# myDRAMTester.net
KiCad netlist of a schematic drawn in EAGLE
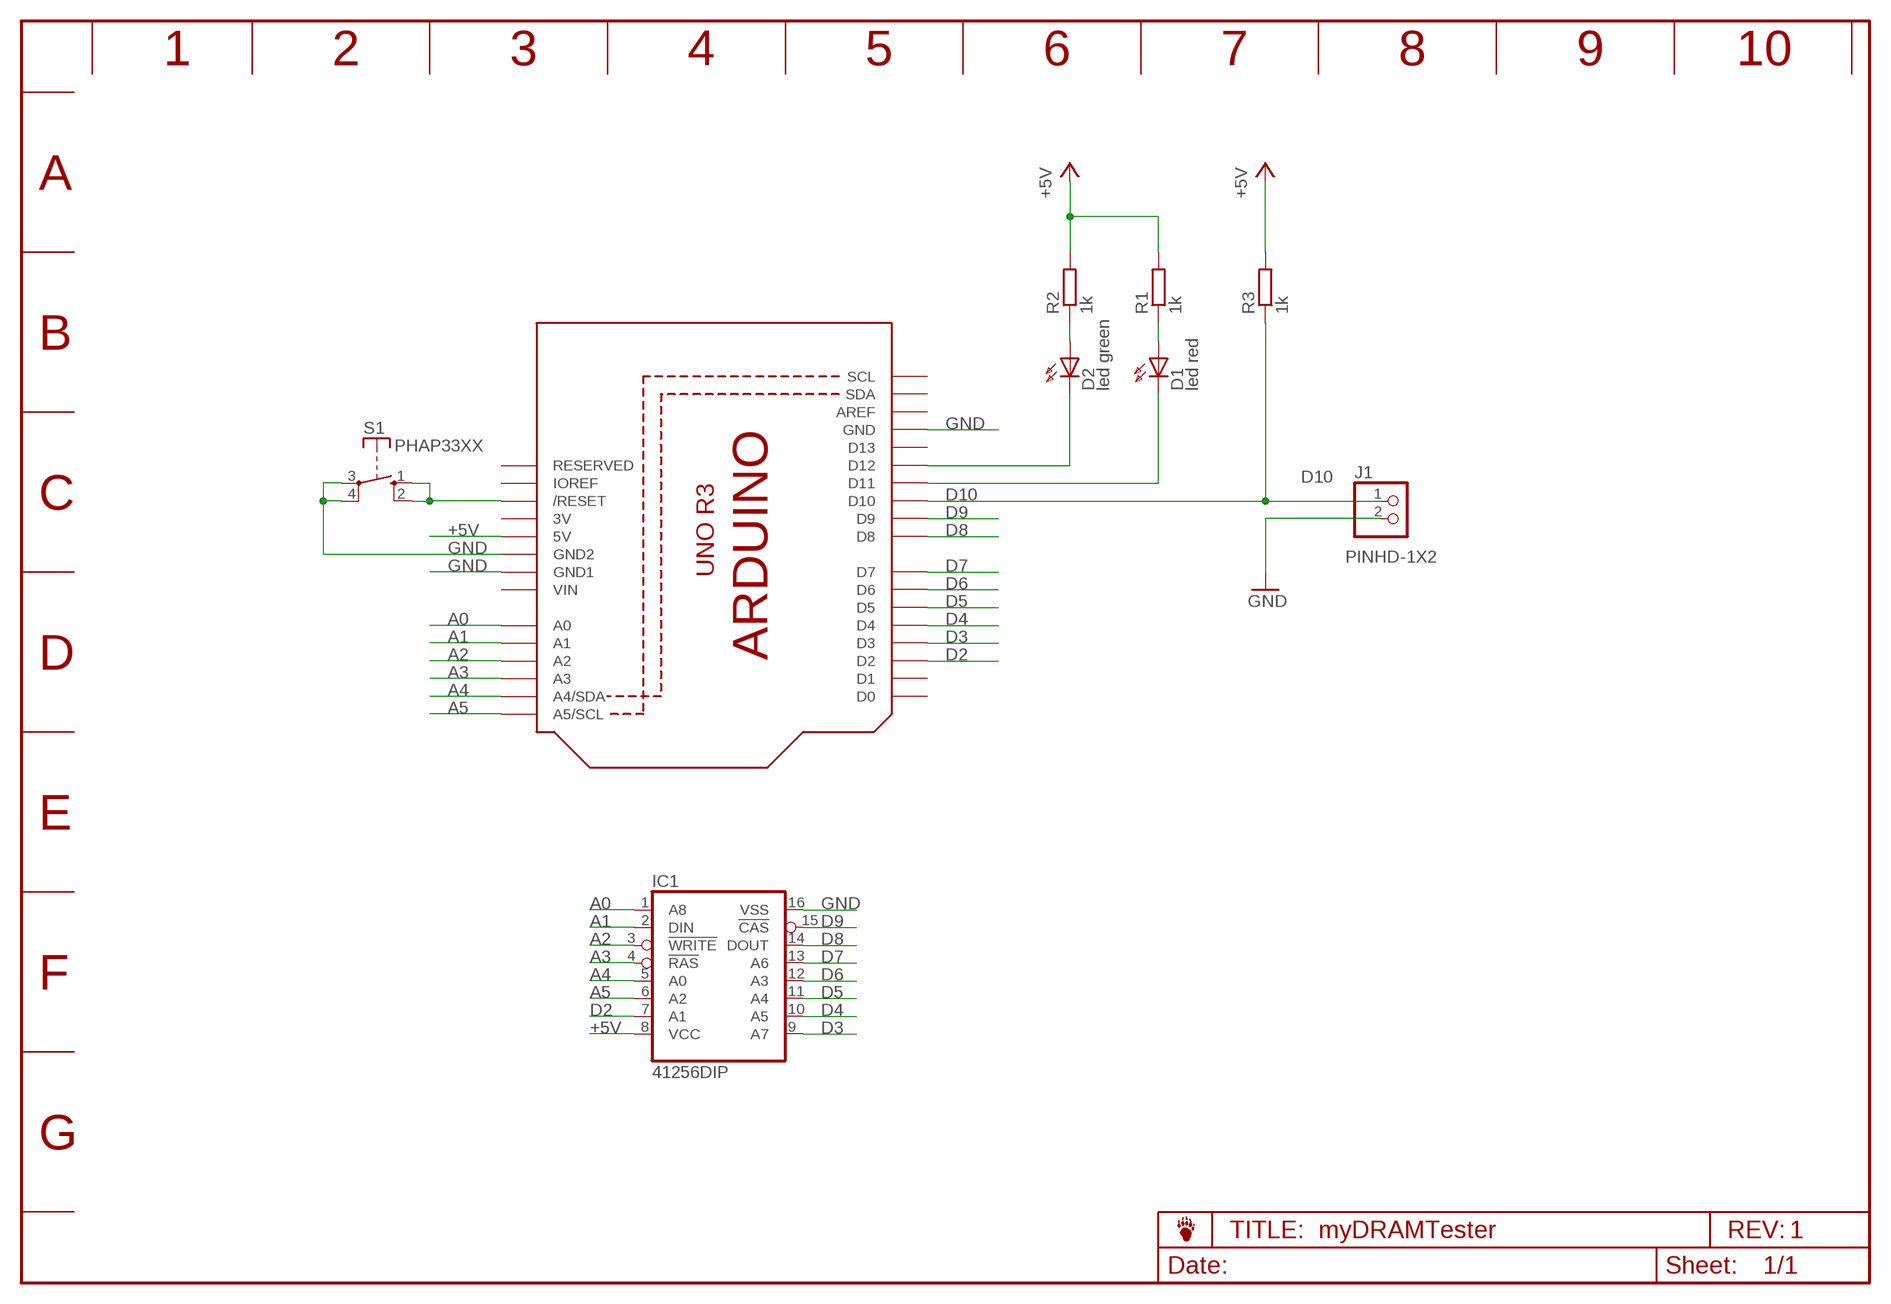
[diagram p0: schematic, sheet 1]

(export (version "E")
  (design (tool "Eeschema 10.0.6"))
  (components
    (comp (ref "D1")
      (value "led red")
      (footprint "eagle-import:LED3MM")
      (libsource (lib "eagle-import") (part "LED3MMS"))
    )
    (comp (ref "D2")
      (value "led green")
      (footprint "eagle-import:LED3MM")
      (libsource (lib "eagle-import") (part "LED3MMS"))
    )
    (comp (ref "IC1")
      (value "41256DIP")
      (footprint "eagle-import:DIL16")
      (libsource (lib "eagle-import") (part "41256DIP"))
    )
    (comp (ref "J1")
      (value "PINHD-1X2")
      (footprint "eagle-import:1X02")
      (libsource (lib "eagle-import") (part "PINHD-1X2"))
    )
    (comp (ref "R1")
      (value "1k")
      (footprint "eagle-import:0207_10")
      (libsource (lib "eagle-import") (part "R-EU_0207/10"))
    )
    (comp (ref "R2")
      (value "1k")
      (footprint "eagle-import:0207_10")
      (libsource (lib "eagle-import") (part "R-EU_0207/10"))
    )
    (comp (ref "R3")
      (value "1k")
      (footprint "eagle-import:0207_10")
      (libsource (lib "eagle-import") (part "R-EU_0207/10"))
    )
    (comp (ref "S1")
      (value "PHAP33XX")
      (footprint "eagle-import:PHAP33XX")
      (libsource (lib "eagle-import") (part "PHAP33XX"))
    )
    (comp (ref "U2")
      (value "ARDUINOR3_BBSMALL")
      (footprint "eagle-import:ARDUINOR3S")
      (libsource (lib "eagle-import") (part "ARDUINOR3_BBSMALL"))
    )
  )
  (nets
    (net (code "1") (name "+5V") (class "Default")
      (node (ref "IC1") (pin "8") (pinfunction "VCC_8") (pintype "input"))
      (node (ref "R1") (pin "2") (pinfunction "2_2") (pintype "passive"))
      (node (ref "R2") (pin "2") (pinfunction "2_2") (pintype "passive"))
      (node (ref "R3") (pin "2") (pinfunction "2_2") (pintype "passive"))
      (node (ref "U2") (pin "5V") (pinfunction "5V_5V") (pintype "power_in"))
    )
    (net (code "2") (name "/3V") (class "Default")
      (node (ref "U2") (pin "3V") (pinfunction "3V_3V") (pintype "power_in"))
    )
    (net (code "3") (name "/A0") (class "Default")
      (node (ref "IC1") (pin "1") (pinfunction "A8_1") (pintype "input"))
      (node (ref "U2") (pin "A0") (pinfunction "A0_A0") (pintype "bidirectional"))
    )
    (net (code "4") (name "/A1") (class "Default")
      (node (ref "IC1") (pin "2") (pinfunction "DIN_2") (pintype "input"))
      (node (ref "U2") (pin "A1") (pinfunction "A1_A1") (pintype "bidirectional"))
    )
    (net (code "5") (name "/A2") (class "Default")
      (node (ref "IC1") (pin "3") (pinfunction "~{WRITE}_3") (pintype "input"))
      (node (ref "U2") (pin "A2") (pinfunction "A2_A2") (pintype "bidirectional"))
    )
    (net (code "6") (name "/A3") (class "Default")
      (node (ref "IC1") (pin "4") (pinfunction "~{RAS}_4") (pintype "input"))
      (node (ref "U2") (pin "A3") (pinfunction "A3_A3") (pintype "bidirectional"))
    )
    (net (code "7") (name "/A4") (class "Default")
      (node (ref "IC1") (pin "5") (pinfunction "A0_5") (pintype "input"))
      (node (ref "U2") (pin "A4") (pinfunction "A4/SDA_A4") (pintype "bidirectional"))
    )
    (net (code "8") (name "/A5") (class "Default")
      (node (ref "IC1") (pin "6") (pinfunction "A2_6") (pintype "input"))
      (node (ref "U2") (pin "A5") (pinfunction "A5/SCL_A5") (pintype "bidirectional"))
    )
    (net (code "9") (name "/D2") (class "Default")
      (node (ref "IC1") (pin "7") (pinfunction "A1_7") (pintype "input"))
      (node (ref "U2") (pin "D2") (pinfunction "D2_D2") (pintype "bidirectional"))
    )
    (net (code "10") (name "/D3") (class "Default")
      (node (ref "IC1") (pin "9") (pinfunction "A7_9") (pintype "tri_state"))
      (node (ref "U2") (pin "D3") (pinfunction "D3_D3") (pintype "bidirectional"))
    )
    (net (code "11") (name "/D4") (class "Default")
      (node (ref "IC1") (pin "10") (pinfunction "A5_10") (pintype "tri_state"))
      (node (ref "U2") (pin "D4") (pinfunction "D4_D4") (pintype "bidirectional"))
    )
    (net (code "12") (name "/D5") (class "Default")
      (node (ref "IC1") (pin "11") (pinfunction "A4_11") (pintype "tri_state"))
      (node (ref "U2") (pin "D5") (pinfunction "D5_D5") (pintype "bidirectional"))
    )
    (net (code "13") (name "/D6") (class "Default")
      (node (ref "IC1") (pin "12") (pinfunction "A3_12") (pintype "tri_state"))
      (node (ref "U2") (pin "D6") (pinfunction "D6_D6") (pintype "bidirectional"))
    )
    (net (code "14") (name "/D7") (class "Default")
      (node (ref "IC1") (pin "13") (pinfunction "A6_13") (pintype "tri_state"))
      (node (ref "U2") (pin "D7") (pinfunction "D7_D7") (pintype "bidirectional"))
    )
    (net (code "15") (name "/D8") (class "Default")
      (node (ref "IC1") (pin "14") (pinfunction "DOUT_14") (pintype "tri_state"))
      (node (ref "U2") (pin "D8") (pinfunction "D8_D8") (pintype "bidirectional"))
    )
    (net (code "16") (name "/D9") (class "Default")
      (node (ref "IC1") (pin "15") (pinfunction "~{CAS}_15") (pintype "tri_state"))
      (node (ref "U2") (pin "D9") (pinfunction "D9_D9") (pintype "bidirectional"))
    )
    (net (code "17") (name "/D10") (class "Default")
      (node (ref "J1") (pin "1") (pinfunction "1_1") (pintype "passive"))
      (node (ref "R3") (pin "1") (pinfunction "1_1") (pintype "passive"))
      (node (ref "U2") (pin "D10") (pinfunction "D10_D10") (pintype "bidirectional"))
    )
    (net (code "18") (name "/VIN") (class "Default")
      (node (ref "U2") (pin "VIN") (pinfunction "VIN_VIN") (pintype "power_in"))
    )
    (net (code "19") (name "GND") (class "Default")
      (node (ref "IC1") (pin "16") (pinfunction "VSS_16") (pintype "tri_state"))
      (node (ref "J1") (pin "2") (pinfunction "2_2") (pintype "passive"))
      (node (ref "S1") (pin "3") (pinfunction "P_3") (pintype "passive"))
      (node (ref "S1") (pin "4") (pinfunction "P_4") (pintype "passive"))
      (node (ref "U2") (pin "GND") (pinfunction "GND_GND") (pintype "power_in"))
      (node (ref "U2") (pin "GND1") (pinfunction "GND1_GND1") (pintype "power_in"))
      (node (ref "U2") (pin "GND2") (pinfunction "GND2_GND2") (pintype "power_in"))
    )
    (net (code "20") (name "Net-(D1-C)") (class "Default")
      (node (ref "D1") (pin "K") (pinfunction "C_K") (pintype "passive"))
      (node (ref "U2") (pin "D11") (pinfunction "D11_D11") (pintype "bidirectional"))
    )
    (net (code "21") (name "Net-(D1-PadA)") (class "Default")
      (node (ref "D1") (pin "A") (pinfunction "A_A") (pintype "passive"))
      (node (ref "R1") (pin "1") (pinfunction "1_1") (pintype "passive"))
    )
    (net (code "22") (name "Net-(D2-C)") (class "Default")
      (node (ref "D2") (pin "K") (pinfunction "C_K") (pintype "passive"))
      (node (ref "U2") (pin "D12") (pinfunction "D12_D12") (pintype "bidirectional"))
    )
    (net (code "23") (name "Net-(D2-PadA)") (class "Default")
      (node (ref "D2") (pin "A") (pinfunction "A_A") (pintype "passive"))
      (node (ref "R2") (pin "1") (pinfunction "1_1") (pintype "passive"))
    )
    (net (code "24") (name "Net-(U2-{slash}RESET)") (class "Default")
      (node (ref "S1") (pin "1") (pinfunction "S_1") (pintype "passive"))
      (node (ref "S1") (pin "2") (pinfunction "S_2") (pintype "passive"))
      (node (ref "U2") (pin "RESET") (pinfunction "/RESET_RESET") (pintype "bidirectional"))
    )
    (net (code "25") (name "unconnected-(U2-PadAREF)") (class "Default")
      (node (ref "U2") (pin "AREF") (pinfunction "AREF_AREF") (pintype "bidirectional"))
    )
    (net (code "26") (name "unconnected-(U2-PadD0)") (class "Default")
      (node (ref "U2") (pin "D0") (pinfunction "D0_D0") (pintype "bidirectional"))
    )
    (net (code "27") (name "unconnected-(U2-PadD1)") (class "Default")
      (node (ref "U2") (pin "D1") (pinfunction "D1_D1") (pintype "bidirectional"))
    )
    (net (code "28") (name "unconnected-(U2-PadD13)") (class "Default")
      (node (ref "U2") (pin "D13") (pinfunction "D13_D13") (pintype "bidirectional"))
    )
    (net (code "29") (name "unconnected-(U2-PadIOREF)") (class "Default")
      (node (ref "U2") (pin "IOREF") (pinfunction "IOREF_IOREF") (pintype "output"))
    )
    (net (code "30") (name "unconnected-(U2-PadRESERVED)") (class "Default")
      (node (ref "U2") (pin "RESERVED") (pinfunction "RESERVED_RESERVED") (pintype "no_connect"))
    )
    (net (code "31") (name "unconnected-(U2-PadSCL)") (class "Default")
      (node (ref "U2") (pin "SCL") (pinfunction "SCL_SCL") (pintype "bidirectional"))
    )
    (net (code "32") (name "unconnected-(U2-PadSDA)") (class "Default")
      (node (ref "U2") (pin "SDA") (pinfunction "SDA_SDA") (pintype "bidirectional"))
    )
  )
)
